# Enclosure_100x68_PBI.net
KiCad netlist of a schematic drawn in EAGLE
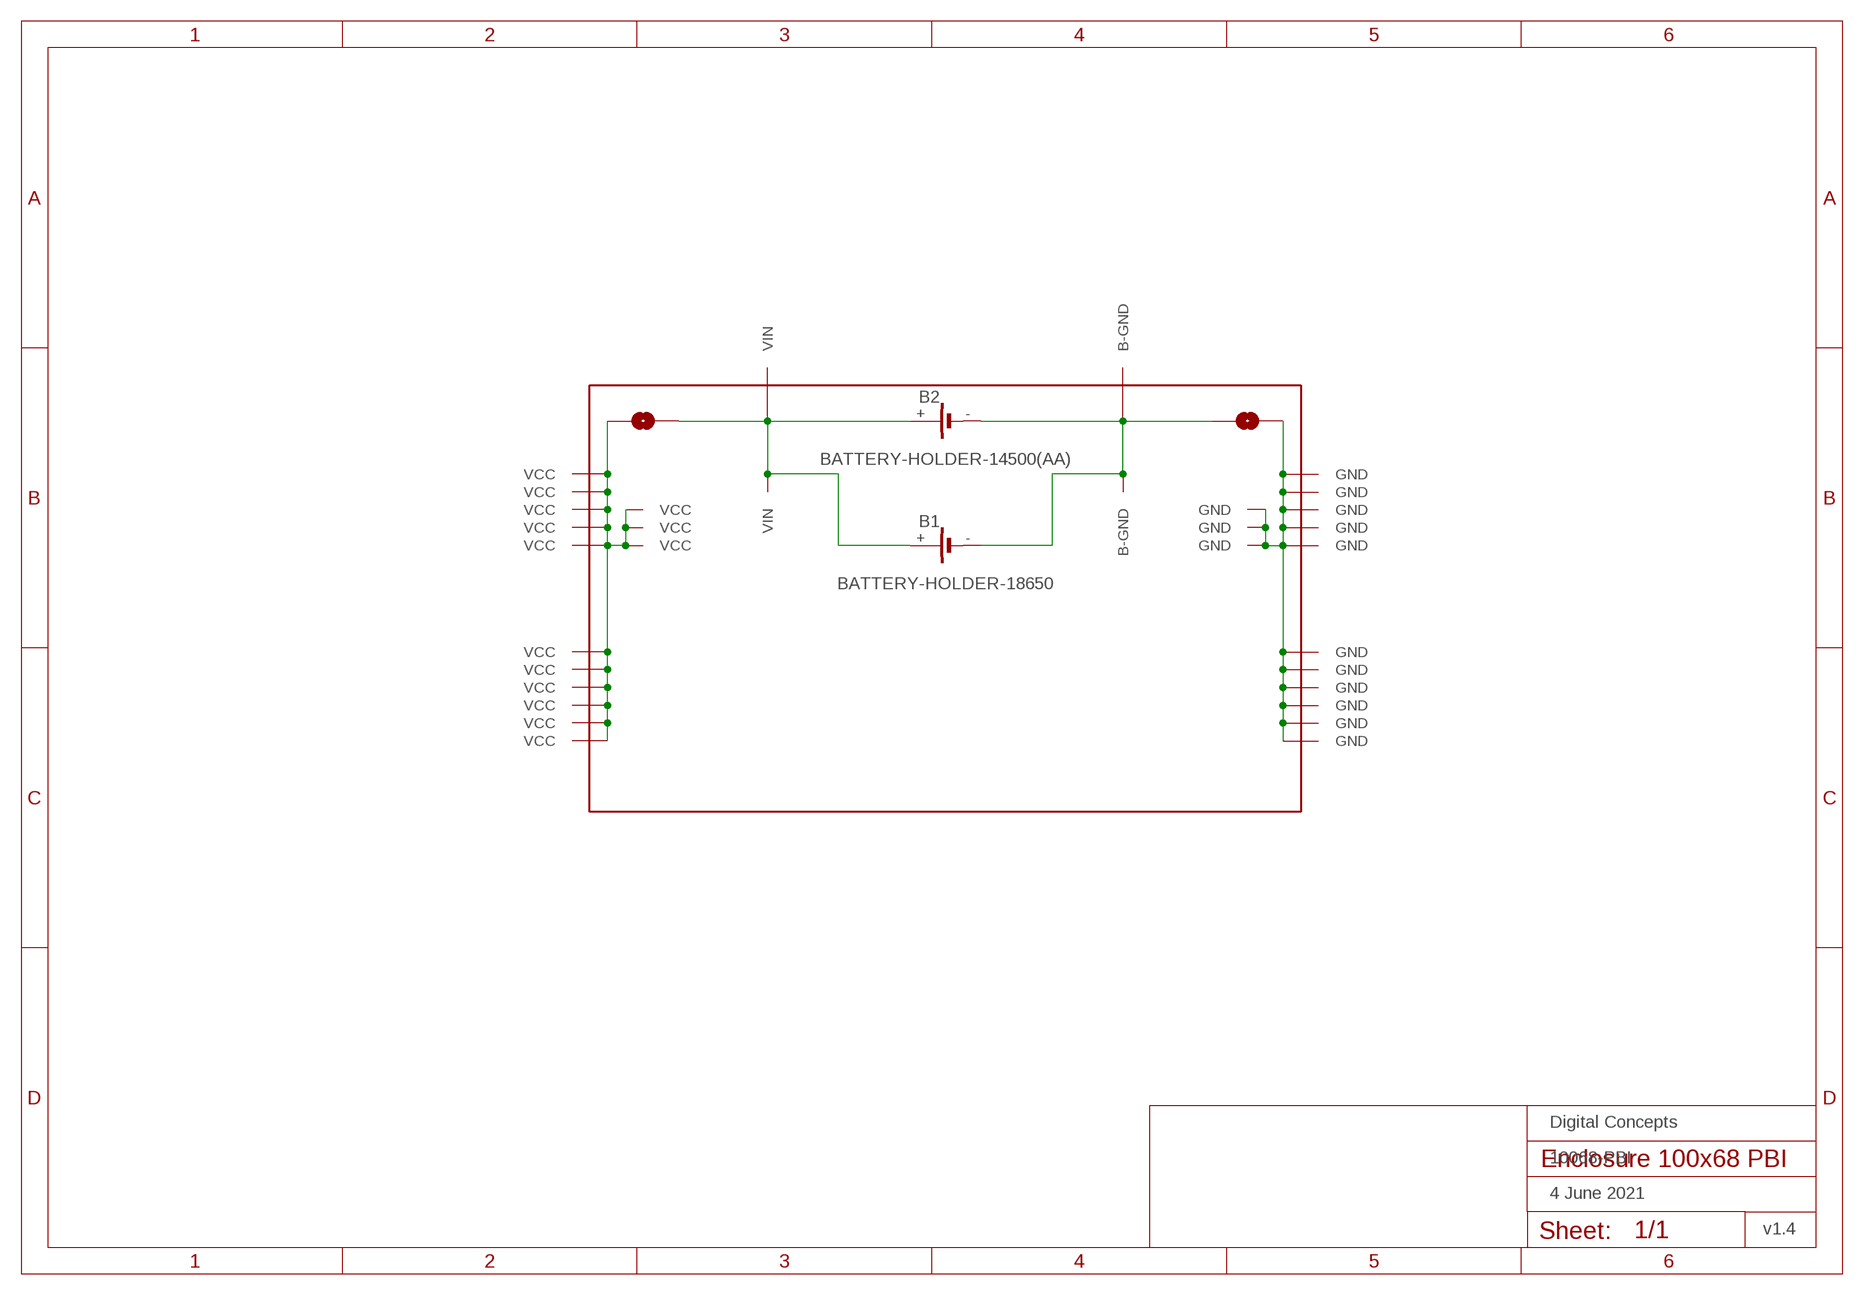
[diagram p0: schematic, sheet 1]

(export (version "E")
  (design (tool "Eeschema 10.0.6"))
  (components
    (comp (ref "B1")
      (value "BATTERY-HOLDER-18650")
      (footprint "eagle-import:BATTERY-18650")
      (libsource (lib "eagle-import") (part "BATTERY-HOLDER-18650"))
    )
    (comp (ref "B2")
      (value "BATTERY-HOLDER-14500(AA)")
      (footprint "eagle-import:BATTERY-14500")
      (libsource (lib "eagle-import") (part "BATTERY-HOLDER-14500(AA)"))
    )
    (comp (ref "P1")
      (value "PROTO-34X22-BAT-SJ-MK2")
      (footprint "eagle-import:PROTO-34X22-BAT-SJ-MK2")
      (libsource (lib "eagle-import") (part "PROTO-34X22-BAT-SJ-MK2"))
    )
  )
  (nets
    (net (code "1") (name "Net-(B1-Pad+)") (class "Default")
      (node (ref "B1") (pin "+") (pinfunction "+_+") (pintype "power_in"))
      (node (ref "B2") (pin "+") (pinfunction "+_+") (pintype "power_in"))
      (node (ref "P1") (pin "P02-17") (pinfunction "VIN_P02-17") (pintype "power_in"))
      (node (ref "P1") (pin "P05-19") (pinfunction "VIN_P05-19") (pintype "power_in"))
      (node (ref "P1") (pin "VIN") (pinfunction "VIN_VIN") (pintype "power_in"))
    )
    (net (code "2") (name "Net-(B1-Pad-)") (class "Default")
      (node (ref "B1") (pin "-") (pinfunction "-_-") (pintype "power_in"))
      (node (ref "B2") (pin "-") (pinfunction "-_-") (pintype "power_in"))
      (node (ref "P1") (pin "B-GND") (pinfunction "B-GND_B-GND") (pintype "power_in"))
      (node (ref "P1") (pin "P30-19") (pinfunction "B-GND_P30-19") (pintype "power_in"))
      (node (ref "P1") (pin "P33-17") (pinfunction "B-GND_P33-17") (pintype "power_in"))
    )
    (net (code "3") (name "Net-(P1-GND-PadP33-13)") (class "Default")
      (node (ref "P1") (pin "GND") (pinfunction "GND_GND") (pintype "power_in"))
      (node (ref "P1") (pin "P33-13") (pinfunction "GND_P33-13") (pintype "power_in"))
      (node (ref "P1") (pin "P33-14") (pinfunction "GND_P33-14") (pintype "power_in"))
      (node (ref "P1") (pin "P33-15") (pinfunction "GND_P33-15") (pintype "power_in"))
      (node (ref "P1") (pin "P34-05") (pinfunction "GND_P34-05") (pintype "power_in"))
      (node (ref "P1") (pin "P34-06") (pinfunction "GND_P34-06") (pintype "power_in"))
      (node (ref "P1") (pin "P34-07") (pinfunction "GND_P34-07") (pintype "power_in"))
      (node (ref "P1") (pin "P34-08") (pinfunction "GND_P34-08") (pintype "power_in"))
      (node (ref "P1") (pin "P34-09") (pinfunction "GND_P34-09") (pintype "power_in"))
      (node (ref "P1") (pin "P34-10") (pinfunction "GND_P34-10") (pintype "power_in"))
      (node (ref "P1") (pin "P34-13") (pinfunction "GND_P34-13") (pintype "power_in"))
      (node (ref "P1") (pin "P34-14") (pinfunction "GND_P34-14") (pintype "power_in"))
      (node (ref "P1") (pin "P34-15") (pinfunction "GND_P34-15") (pintype "power_in"))
      (node (ref "P1") (pin "P34-16") (pinfunction "GND_P34-16") (pintype "power_in"))
      (node (ref "P1") (pin "P34-17") (pinfunction "GND_P34-17") (pintype "power_in"))
    )
    (net (code "4") (name "Net-(P1-PadVCC)") (class "Default")
      (node (ref "P1") (pin "P01-05") (pinfunction "VCC_P01-05") (pintype "power_in"))
      (node (ref "P1") (pin "P01-06") (pinfunction "VCC_P01-06") (pintype "power_in"))
      (node (ref "P1") (pin "P01-07") (pinfunction "VCC_P01-07") (pintype "power_in"))
      (node (ref "P1") (pin "P01-08") (pinfunction "VCC_P01-08") (pintype "power_in"))
      (node (ref "P1") (pin "P01-09") (pinfunction "VCC_P01-09") (pintype "power_in"))
      (node (ref "P1") (pin "P01-10") (pinfunction "VCC_P01-10") (pintype "power_in"))
      (node (ref "P1") (pin "P01-13") (pinfunction "VCC_P01-13") (pintype "power_in"))
      (node (ref "P1") (pin "P01-14") (pinfunction "VCC_P01-14") (pintype "power_in"))
      (node (ref "P1") (pin "P01-15") (pinfunction "VCC_P01-15") (pintype "power_in"))
      (node (ref "P1") (pin "P01-16") (pinfunction "VCC_P01-16") (pintype "power_in"))
      (node (ref "P1") (pin "P01-17") (pinfunction "VCC_P01-17") (pintype "power_in"))
      (node (ref "P1") (pin "P02-13") (pinfunction "VCC_P02-13") (pintype "power_in"))
      (node (ref "P1") (pin "P02-14") (pinfunction "VCC_P02-14") (pintype "power_in"))
      (node (ref "P1") (pin "P02-15") (pinfunction "VCC_P02-15") (pintype "power_in"))
      (node (ref "P1") (pin "VCC") (pinfunction "VCC_VCC") (pintype "power_in"))
    )
  )
)
